# SimplePiddy.net
KiCad netlist of a schematic drawn in EAGLE
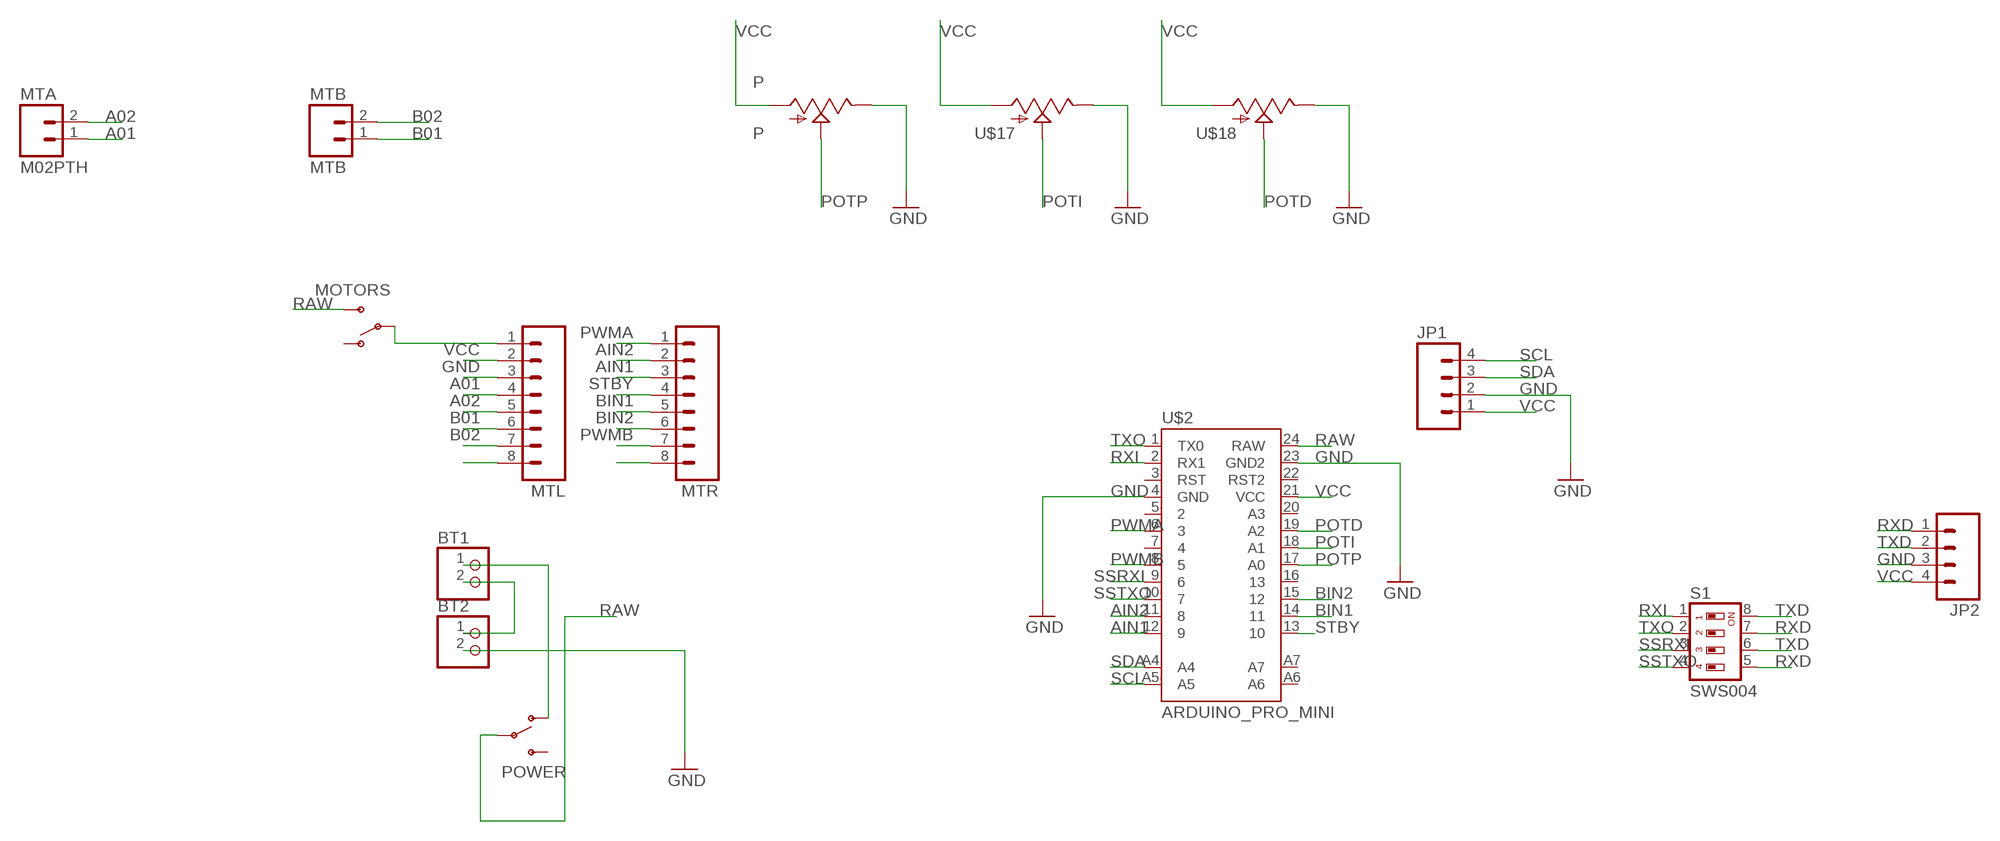
[diagram p0: schematic, sheet 1]

(export (version "E")
  (design (tool "Eeschema 10.0.6"))
  (components
    (comp (ref "BT1")
      (value "JST_2PIN")
      (footprint "eagle-import:JSTPH2STRAIGHT")
      (libsource (lib "eagle-import") (part "JST_2PIN"))
    )
    (comp (ref "BT2")
      (value "JST_2PIN")
      (footprint "eagle-import:JSTPH2STRAIGHT")
      (libsource (lib "eagle-import") (part "JST_2PIN"))
    )
    (comp (ref "JP1")
      (value "M04PTH")
      (footprint "eagle-import:1X04")
      (libsource (lib "eagle-import") (part "M04PTH"))
    )
    (comp (ref "JP2")
      (value "M04PTH")
      (footprint "eagle-import:1X04")
      (libsource (lib "eagle-import") (part "M04PTH"))
    )
    (comp (ref "MOTORS")
      (value "SWITCH-SPDTPTH")
      (footprint "eagle-import:SWITCH-SPDT")
      (libsource (lib "eagle-import") (part "SWITCH-SPDTPTH"))
    )
    (comp (ref "MTA")
      (value "M02PTH")
      (footprint "eagle-import:1X02")
      (libsource (lib "eagle-import") (part "M02PTH"))
    )
    (comp (ref "MTB")
      (value "MTB")
      (footprint "eagle-import:1X02")
      (libsource (lib "eagle-import") (part "M02PTH"))
    )
    (comp (ref "MTL")
      (value "M08LONGPADS")
      (footprint "eagle-import:1X08_LONGPADS")
      (libsource (lib "eagle-import") (part "M08LONGPADS"))
    )
    (comp (ref "MTR")
      (value "M08LONGPADS")
      (footprint "eagle-import:1X08_LONGPADS")
      (libsource (lib "eagle-import") (part "M08LONGPADS"))
    )
    (comp (ref "P")
      (value "P")
      (footprint "eagle-import:ALPS_POT")
      (libsource (lib "eagle-import") (part "POT"))
    )
    (comp (ref "POWER")
      (value "SWITCH-SPDTPTH")
      (footprint "eagle-import:SWITCH-SPDT")
      (libsource (lib "eagle-import") (part "SWITCH-SPDTPTH"))
    )
    (comp (ref "S1")
      (value "SWS004")
      (footprint "eagle-import:SMS-004")
      (libsource (lib "eagle-import") (part "SWS004"))
    )
    (comp (ref "U$2")
      (value "ARDUINO_PRO_MINI")
      (footprint "eagle-import:ARDUINO_PRO_MINI")
      (libsource (lib "eagle-import") (part "ARDUINO_PRO_MINI"))
    )
    (comp (ref "U$17")
      (value "POT")
      (footprint "eagle-import:ALPS_POT")
      (libsource (lib "eagle-import") (part "POT"))
    )
    (comp (ref "U$18")
      (value "POT")
      (footprint "eagle-import:ALPS_POT")
      (libsource (lib "eagle-import") (part "POT"))
    )
  )
  (nets
    (net (code "1") (name "/A01") (class "Default")
      (node (ref "MTA") (pin "1") (pinfunction "1_1") (pintype "passive"))
      (node (ref "MTL") (pin "4") (pinfunction "4_4") (pintype "passive"))
    )
    (net (code "2") (name "/A02") (class "Default")
      (node (ref "MTA") (pin "2") (pinfunction "2_2") (pintype "passive"))
      (node (ref "MTL") (pin "5") (pinfunction "5_5") (pintype "passive"))
    )
    (net (code "3") (name "/AIN1") (class "Default")
      (node (ref "MTR") (pin "3") (pinfunction "3_3") (pintype "passive"))
      (node (ref "U$2") (pin "12") (pinfunction "9_12") (pintype "bidirectional"))
    )
    (net (code "4") (name "/AIN2") (class "Default")
      (node (ref "MTR") (pin "2") (pinfunction "2_2") (pintype "passive"))
      (node (ref "U$2") (pin "11") (pinfunction "8_11") (pintype "bidirectional"))
    )
    (net (code "5") (name "/B01") (class "Default")
      (node (ref "MTB") (pin "1") (pinfunction "1_1") (pintype "passive"))
      (node (ref "MTL") (pin "6") (pinfunction "6_6") (pintype "passive"))
    )
    (net (code "6") (name "/B02") (class "Default")
      (node (ref "MTB") (pin "2") (pinfunction "2_2") (pintype "passive"))
      (node (ref "MTL") (pin "7") (pinfunction "7_7") (pintype "passive"))
    )
    (net (code "7") (name "/BIN1") (class "Default")
      (node (ref "MTR") (pin "5") (pinfunction "5_5") (pintype "passive"))
      (node (ref "U$2") (pin "14") (pinfunction "11_14") (pintype "bidirectional"))
    )
    (net (code "8") (name "/BIN2") (class "Default")
      (node (ref "MTR") (pin "6") (pinfunction "6_6") (pintype "passive"))
      (node (ref "U$2") (pin "15") (pinfunction "12_15") (pintype "bidirectional"))
    )
    (net (code "9") (name "/POTD") (class "Default")
      (node (ref "U$18") (pin "P$2") (pinfunction "S_P$2") (pintype "passive"))
      (node (ref "U$2") (pin "19") (pinfunction "A2_19") (pintype "bidirectional"))
    )
    (net (code "10") (name "/POTI") (class "Default")
      (node (ref "U$17") (pin "P$2") (pinfunction "S_P$2") (pintype "passive"))
      (node (ref "U$2") (pin "18") (pinfunction "A1_18") (pintype "bidirectional"))
    )
    (net (code "11") (name "/POTP") (class "Default")
      (node (ref "P") (pin "P$2") (pinfunction "S_P$2") (pintype "passive"))
      (node (ref "U$2") (pin "17") (pinfunction "A0_17") (pintype "bidirectional"))
    )
    (net (code "12") (name "/PWMA") (class "Default")
      (node (ref "MTR") (pin "1") (pinfunction "1_1") (pintype "passive"))
      (node (ref "U$2") (pin "6") (pinfunction "3_6") (pintype "bidirectional"))
    )
    (net (code "13") (name "/PWMB") (class "Default")
      (node (ref "MTR") (pin "7") (pinfunction "7_7") (pintype "passive"))
      (node (ref "U$2") (pin "8") (pinfunction "5_8") (pintype "bidirectional"))
    )
    (net (code "14") (name "/RAW") (class "Default")
      (node (ref "MOTORS") (pin "3") (pinfunction "S_3") (pintype "passive"))
      (node (ref "POWER") (pin "2") (pinfunction "P_2") (pintype "passive"))
      (node (ref "U$2") (pin "24") (pinfunction "RAW_24") (pintype "bidirectional"))
    )
    (net (code "15") (name "/RXD") (class "Default")
      (node (ref "JP2") (pin "1") (pinfunction "1_1") (pintype "passive"))
      (node (ref "S1") (pin "5") (pinfunction "5_5") (pintype "passive"))
      (node (ref "S1") (pin "7") (pinfunction "7_7") (pintype "passive"))
    )
    (net (code "16") (name "/RXI") (class "Default")
      (node (ref "S1") (pin "1") (pinfunction "1_1") (pintype "passive"))
      (node (ref "U$2") (pin "2") (pinfunction "RX1_2") (pintype "bidirectional"))
    )
    (net (code "17") (name "/SCL") (class "Default")
      (node (ref "JP1") (pin "4") (pinfunction "4_4") (pintype "passive"))
      (node (ref "U$2") (pin "A5") (pinfunction "A5_A5") (pintype "bidirectional"))
    )
    (net (code "18") (name "/SDA") (class "Default")
      (node (ref "JP1") (pin "3") (pinfunction "3_3") (pintype "passive"))
      (node (ref "U$2") (pin "A4") (pinfunction "A4_A4") (pintype "bidirectional"))
    )
    (net (code "19") (name "/SSRXI") (class "Default")
      (node (ref "S1") (pin "3") (pinfunction "3_3") (pintype "passive"))
      (node (ref "U$2") (pin "9") (pinfunction "6_9") (pintype "bidirectional"))
    )
    (net (code "20") (name "/SSTXO") (class "Default")
      (node (ref "S1") (pin "4") (pinfunction "4_4") (pintype "passive"))
      (node (ref "U$2") (pin "10") (pinfunction "7_10") (pintype "bidirectional"))
    )
    (net (code "21") (name "/STBY") (class "Default")
      (node (ref "MTR") (pin "4") (pinfunction "4_4") (pintype "passive"))
      (node (ref "U$2") (pin "13") (pinfunction "10_13") (pintype "bidirectional"))
    )
    (net (code "22") (name "/TXD") (class "Default")
      (node (ref "JP2") (pin "2") (pinfunction "2_2") (pintype "passive"))
      (node (ref "S1") (pin "6") (pinfunction "6_6") (pintype "passive"))
      (node (ref "S1") (pin "8") (pinfunction "8_8") (pintype "passive"))
    )
    (net (code "23") (name "/TXO") (class "Default")
      (node (ref "S1") (pin "2") (pinfunction "2_2") (pintype "passive"))
      (node (ref "U$2") (pin "1") (pinfunction "TX0_1") (pintype "bidirectional"))
    )
    (net (code "24") (name "/VCC") (class "Default")
      (node (ref "JP1") (pin "1") (pinfunction "1_1") (pintype "passive"))
      (node (ref "JP2") (pin "4") (pinfunction "4_4") (pintype "passive"))
      (node (ref "MTL") (pin "2") (pinfunction "2_2") (pintype "passive"))
      (node (ref "P") (pin "P$3") (pinfunction "A_P$3") (pintype "passive"))
      (node (ref "U$17") (pin "P$3") (pinfunction "A_P$3") (pintype "passive"))
      (node (ref "U$18") (pin "P$3") (pinfunction "A_P$3") (pintype "passive"))
      (node (ref "U$2") (pin "21") (pinfunction "VCC_21") (pintype "bidirectional"))
    )
    (net (code "25") (name "GND") (class "Default")
      (node (ref "BT2") (pin "2") (pinfunction "2_2") (pintype "passive"))
      (node (ref "JP1") (pin "2") (pinfunction "2_2") (pintype "passive"))
      (node (ref "JP2") (pin "3") (pinfunction "3_3") (pintype "passive"))
      (node (ref "MTL") (pin "3") (pinfunction "3_3") (pintype "passive"))
      (node (ref "MTL") (pin "8") (pinfunction "8_8") (pintype "passive"))
      (node (ref "MTR") (pin "8") (pinfunction "8_8") (pintype "passive"))
      (node (ref "P") (pin "P$1") (pinfunction "E_P$1") (pintype "passive"))
      (node (ref "U$17") (pin "P$1") (pinfunction "E_P$1") (pintype "passive"))
      (node (ref "U$18") (pin "P$1") (pinfunction "E_P$1") (pintype "passive"))
      (node (ref "U$2") (pin "23") (pinfunction "GND2_23") (pintype "bidirectional"))
      (node (ref "U$2") (pin "4") (pinfunction "GND_4") (pintype "bidirectional"))
    )
    (net (code "26") (name "Net-(BT1-Pad2)") (class "Default")
      (node (ref "BT1") (pin "2") (pinfunction "2_2") (pintype "passive"))
      (node (ref "BT2") (pin "1") (pinfunction "1_1") (pintype "passive"))
    )
    (net (code "27") (name "Net-(MOTORS-P)") (class "Default")
      (node (ref "MOTORS") (pin "2") (pinfunction "P_2") (pintype "passive"))
      (node (ref "MTL") (pin "1") (pinfunction "1_1") (pintype "passive"))
    )
    (net (code "28") (name "Net-(POWER-O)") (class "Default")
      (node (ref "BT1") (pin "1") (pinfunction "1_1") (pintype "passive"))
      (node (ref "POWER") (pin "1") (pinfunction "O_1") (pintype "passive"))
    )
    (net (code "29") (name "unconnected-(MOTORS-O-Pad1)") (class "Default")
      (node (ref "MOTORS") (pin "1") (pinfunction "O_1") (pintype "passive"))
    )
    (net (code "30") (name "unconnected-(POWER-S-Pad3)") (class "Default")
      (node (ref "POWER") (pin "3") (pinfunction "S_3") (pintype "passive"))
    )
    (net (code "31") (name "unconnected-(U$2-2-Pad5)") (class "Default")
      (node (ref "U$2") (pin "5") (pinfunction "2_5") (pintype "bidirectional"))
    )
    (net (code "32") (name "unconnected-(U$2-4-Pad7)") (class "Default")
      (node (ref "U$2") (pin "7") (pinfunction "4_7") (pintype "bidirectional"))
    )
    (net (code "33") (name "unconnected-(U$2-13-Pad16)") (class "Default")
      (node (ref "U$2") (pin "16") (pinfunction "13_16") (pintype "bidirectional"))
    )
    (net (code "34") (name "unconnected-(U$2-A3-Pad20)") (class "Default")
      (node (ref "U$2") (pin "20") (pinfunction "A3_20") (pintype "bidirectional"))
    )
    (net (code "35") (name "unconnected-(U$2-PadA6)") (class "Default")
      (node (ref "U$2") (pin "A6") (pinfunction "A6_A6") (pintype "bidirectional"))
    )
    (net (code "36") (name "unconnected-(U$2-PadA7)") (class "Default")
      (node (ref "U$2") (pin "A7") (pinfunction "A7_A7") (pintype "bidirectional"))
    )
    (net (code "37") (name "unconnected-(U$2-RST-Pad3)") (class "Default")
      (node (ref "U$2") (pin "3") (pinfunction "RST_3") (pintype "bidirectional"))
    )
    (net (code "38") (name "unconnected-(U$2-RST2-Pad22)") (class "Default")
      (node (ref "U$2") (pin "22") (pinfunction "RST2_22") (pintype "bidirectional"))
    )
  )
)
